# M0519SD3AE_breakout_v1.net
KiCad netlist of a schematic drawn in EAGLE
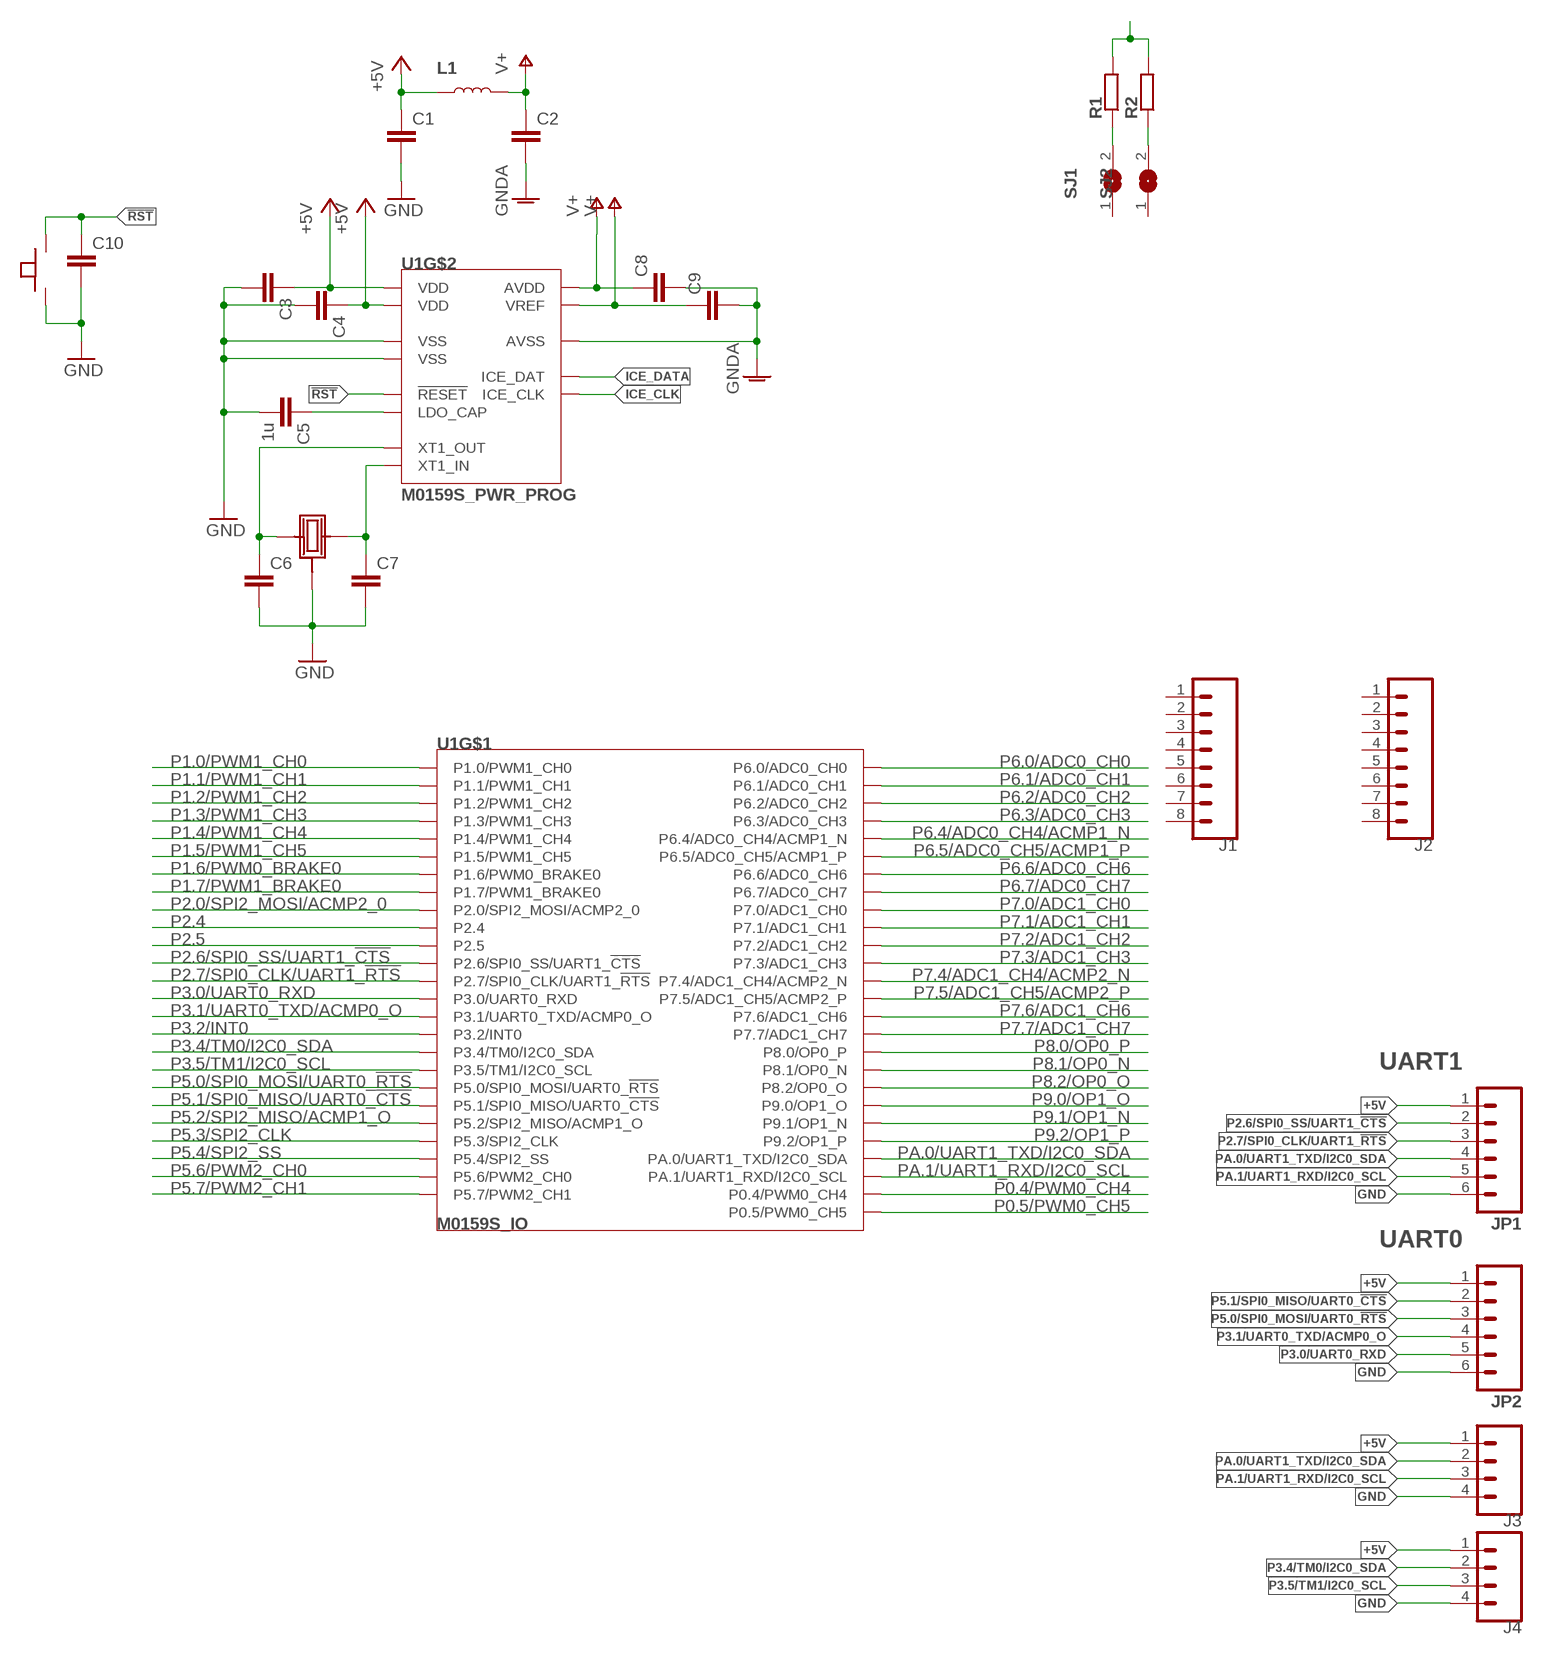
[diagram p0: schematic, sheet 1]

(export (version "E")
  (design (tool "Eeschema 10.0.6"))
  (components
    (comp (ref "C1")
      (value "CAP0603-CAP")
      (footprint "eagle-import:0603-CAP")
      (libsource (lib "eagle-import") (part "CAP0603-CAP"))
    )
    (comp (ref "C2")
      (value "CAP0603-CAP")
      (footprint "eagle-import:0603-CAP")
      (libsource (lib "eagle-import") (part "CAP0603-CAP"))
    )
    (comp (ref "C3")
      (value "CAP0603-CAP")
      (footprint "eagle-import:0603-CAP")
      (libsource (lib "eagle-import") (part "CAP0603-CAP"))
    )
    (comp (ref "C4")
      (value "CAP0603-CAP")
      (footprint "eagle-import:0603-CAP")
      (libsource (lib "eagle-import") (part "CAP0603-CAP"))
    )
    (comp (ref "C5")
      (value "1u")
      (footprint "eagle-import:0603-CAP")
      (libsource (lib "eagle-import") (part "CAP0603-CAP"))
    )
    (comp (ref "C6")
      (value "CAP0603-CAP")
      (footprint "eagle-import:0603-CAP")
      (libsource (lib "eagle-import") (part "CAP0603-CAP"))
    )
    (comp (ref "C7")
      (value "CAP0603-CAP")
      (footprint "eagle-import:0603-CAP")
      (libsource (lib "eagle-import") (part "CAP0603-CAP"))
    )
    (comp (ref "C8")
      (value "CAP0603-CAP")
      (footprint "eagle-import:0603-CAP")
      (libsource (lib "eagle-import") (part "CAP0603-CAP"))
    )
    (comp (ref "C9")
      (value "CAP0603-CAP")
      (footprint "eagle-import:0603-CAP")
      (libsource (lib "eagle-import") (part "CAP0603-CAP"))
    )
    (comp (ref "C10")
      (value "CAP0603-CAP")
      (footprint "eagle-import:0603-CAP")
      (libsource (lib "eagle-import") (part "CAP0603-CAP"))
    )
    (comp (ref "J1")
      (value "M08")
      (footprint "eagle-import:1X08")
      (libsource (lib "eagle-import") (part "M08"))
    )
    (comp (ref "J2")
      (value "M08")
      (footprint "eagle-import:1X08")
      (libsource (lib "eagle-import") (part "M08"))
    )
    (comp (ref "J3")
      (value "M04")
      (footprint "eagle-import:1X04")
      (libsource (lib "eagle-import") (part "M04"))
    )
    (comp (ref "J4")
      (value "M04")
      (footprint "eagle-import:1X04")
      (libsource (lib "eagle-import") (part "M04"))
    )
    (comp (ref "JP1")
      (value "M06LOCK")
      (footprint "eagle-import:1X06_LOCK")
      (libsource (lib "eagle-import") (part "M06LOCK"))
    )
    (comp (ref "JP2")
      (value "M06LOCK")
      (footprint "eagle-import:1X06_LOCK")
      (libsource (lib "eagle-import") (part "M06LOCK"))
    )
    (comp (ref "L1")
      (value "INDUCTOR_FB")
      (footprint "eagle-import:0603-FB")
      (libsource (lib "eagle-import") (part "INDUCTOR_FB"))
    )
    (comp (ref "R1")
      (value "RESISTOR0603-RES")
      (footprint "eagle-import:0603-RES")
      (libsource (lib "eagle-import") (part "RESISTOR0603-RES"))
    )
    (comp (ref "R2")
      (value "RESISTOR0603-RES")
      (footprint "eagle-import:0603-RES")
      (libsource (lib "eagle-import") (part "RESISTOR0603-RES"))
    )
    (comp (ref "SJ1") (value "SJ") (footprint "eagle-import:SJ") (libsource (lib "eagle-import") (part "SJ")))
    (comp (ref "SJ2") (value "SJ") (footprint "eagle-import:SJ") (libsource (lib "eagle-import") (part "SJ")))
    (comp (ref "U$1")
      (value "CRYSTAL_EPSON")
      (footprint "eagle-import:TSX3225")
      (libsource (lib "eagle-import") (part "CRYSTAL_EPSON"))
    )
    (comp (ref "U$2")
      (value "95C06B2GWRT")
      (footprint "eagle-import:PUSH-BUTTON-95C06B2GWRT")
      (libsource (lib "eagle-import") (part "95C06B2GWRT"))
    )
    (comp (ref "U1")
      (value "M0159S")
      (footprint "eagle-import:LQFP-64_7MMX7MMX1.6MM")
      (libsource (lib "eagle-import") (part "M0159S"))
    )
  )
  (nets
    (net (code "1") (name "+5V") (class "Default")
      (node (ref "C1") (pin "1") (pinfunction "1_1") (pintype "passive"))
      (node (ref "C3") (pin "1") (pinfunction "1_1") (pintype "passive"))
      (node (ref "C4") (pin "1") (pinfunction "1_1") (pintype "passive"))
      (node (ref "J3") (pin "1") (pinfunction "1_1") (pintype "passive"))
      (node (ref "J4") (pin "1") (pinfunction "1_1") (pintype "passive"))
      (node (ref "JP1") (pin "1") (pinfunction "1_1") (pintype "passive"))
      (node (ref "JP2") (pin "1") (pinfunction "1_1") (pintype "passive"))
      (node (ref "L1") (pin "1") (pinfunction "1_1") (pintype "passive"))
      (node (ref "U1") (pin "21") (pinfunction "VDD_21") (pintype "power_in"))
      (node (ref "U1") (pin "6") (pinfunction "VDD_6") (pintype "power_in"))
    )
    (net (code "2") (name "/P0.4{slash}PWM0_CH4") (class "Default")
      (node (ref "U1") (pin "30") (pinfunction "P0.4/PWM0_CH4_30") (pintype "bidirectional"))
    )
    (net (code "3") (name "/P0.5{slash}PWM0_CH5") (class "Default")
      (node (ref "U1") (pin "29") (pinfunction "P0.5/PWM0_CH5_29") (pintype "bidirectional"))
    )
    (net (code "4") (name "/P1.0{slash}PWM1_CH0") (class "Default")
      (node (ref "U1") (pin "18") (pinfunction "P1.0/PWM1_CH0_18") (pintype "bidirectional"))
    )
    (net (code "5") (name "/P1.1{slash}PWM1_CH1") (class "Default")
      (node (ref "U1") (pin "17") (pinfunction "P1.1/PWM1_CH1_17") (pintype "bidirectional"))
    )
    (net (code "6") (name "/P1.2{slash}PWM1_CH2") (class "Default")
      (node (ref "U1") (pin "16") (pinfunction "P1.2/PWM1_CH2_16") (pintype "bidirectional"))
    )
    (net (code "7") (name "/P1.3{slash}PWM1_CH3") (class "Default")
      (node (ref "U1") (pin "15") (pinfunction "P1.3/PWM1_CH3_15") (pintype "bidirectional"))
    )
    (net (code "8") (name "/P1.4{slash}PWM1_CH4") (class "Default")
      (node (ref "U1") (pin "14") (pinfunction "P1.4/PWM1_CH4_14") (pintype "bidirectional"))
    )
    (net (code "9") (name "/P1.5{slash}PWM1_CH5") (class "Default")
      (node (ref "U1") (pin "13") (pinfunction "P1.5/PWM1_CH5_13") (pintype "bidirectional"))
    )
    (net (code "10") (name "/P1.6{slash}PWM0_BRAKE0") (class "Default")
      (node (ref "U1") (pin "12") (pinfunction "P1.6/PWM0_BRAKE0_12") (pintype "bidirectional"))
    )
    (net (code "11") (name "/P1.7{slash}PWM1_BRAKE0") (class "Default")
      (node (ref "U1") (pin "4") (pinfunction "P1.7/PWM1_BRAKE0_4") (pintype "bidirectional"))
    )
    (net (code "12") (name "/P2.0{slash}SPI2_MOSI{slash}ACMP2_0") (class "Default")
      (node (ref "U1") (pin "31") (pinfunction "P2.0/SPI2_MOSI/ACMP2_0_31") (pintype "bidirectional"))
    )
    (net (code "13") (name "/P2.4") (class "Default")
      (node (ref "U1") (pin "28") (pinfunction "P2.4_28") (pintype "bidirectional"))
    )
    (net (code "14") (name "/P2.5") (class "Default")
      (node (ref "U1") (pin "27") (pinfunction "P2.5_27") (pintype "bidirectional"))
    )
    (net (code "15") (name "/P2.6{slash}SPI0_SS{slash}UART1_~{CTS}") (class "Default")
      (node (ref "JP1") (pin "2") (pinfunction "2_2") (pintype "passive"))
      (node (ref "U1") (pin "26") (pinfunction "P2.6/SPI0_SS/UART1_~{CTS}_26") (pintype "bidirectional"))
    )
    (net (code "16") (name "/P2.7{slash}SPI0_CLK{slash}UART1_~{RTS}") (class "Default")
      (node (ref "JP1") (pin "3") (pinfunction "3_3") (pintype "passive"))
      (node (ref "U1") (pin "25") (pinfunction "P2.7/SPI0_CLK/UART1_~{RTS}_25") (pintype "bidirectional"))
    )
    (net (code "17") (name "/P3.2{slash}INT0") (class "Default")
      (node (ref "U1") (pin "3") (pinfunction "P3.2/INT0_3") (pintype "bidirectional"))
    )
    (net (code "18") (name "/P5.0{slash}SPI0_MOSI{slash}UART0_~{RTS}") (class "Default")
      (node (ref "JP2") (pin "3") (pinfunction "3_3") (pintype "passive"))
      (node (ref "U1") (pin "23") (pinfunction "P5.0/SPI0_MOSI/UART0_~{RTS}_23") (pintype "bidirectional"))
    )
    (net (code "19") (name "/P5.1{slash}SPI0_MISO{slash}UART0_~{CTS}") (class "Default")
      (node (ref "JP2") (pin "2") (pinfunction "2_2") (pintype "passive"))
      (node (ref "U1") (pin "24") (pinfunction "P5.1/SPI0_MISO/UART0_~{CTS}_24") (pintype "bidirectional"))
    )
    (net (code "20") (name "/P5.2{slash}SPI2_MISO{slash}ACMP1_O") (class "Default")
      (node (ref "U1") (pin "32") (pinfunction "P5.2/SPI2_MISO/ACMP1_O_32") (pintype "bidirectional"))
    )
    (net (code "21") (name "/P5.3{slash}SPI2_CLK") (class "Default")
      (node (ref "U1") (pin "33") (pinfunction "P5.3/SPI2_CLK_33") (pintype "bidirectional"))
    )
    (net (code "22") (name "/P5.4{slash}SPI2_SS") (class "Default")
      (node (ref "U1") (pin "34") (pinfunction "P5.4/SPI2_SS_34") (pintype "bidirectional"))
    )
    (net (code "23") (name "/P5.6{slash}PWM2_CH0") (class "Default")
      (node (ref "U1") (pin "11") (pinfunction "P5.6/PWM2_CH0_11") (pintype "bidirectional"))
    )
    (net (code "24") (name "/P5.7{slash}PWM2_CH1") (class "Default")
      (node (ref "U1") (pin "10") (pinfunction "P5.7/PWM2_CH1_10") (pintype "bidirectional"))
    )
    (net (code "25") (name "/P6.0{slash}ADC0_CH0") (class "Default")
      (node (ref "U1") (pin "42") (pinfunction "P6.0/ADC0_CH0_42") (pintype "bidirectional"))
    )
    (net (code "26") (name "/P6.1{slash}ADC0_CH1") (class "Default")
      (node (ref "U1") (pin "41") (pinfunction "P6.1/ADC0_CH1_41") (pintype "bidirectional"))
    )
    (net (code "27") (name "/P6.2{slash}ADC0_CH2") (class "Default")
      (node (ref "U1") (pin "40") (pinfunction "P6.2/ADC0_CH2_40") (pintype "bidirectional"))
    )
    (net (code "28") (name "/P6.3{slash}ADC0_CH3") (class "Default")
      (node (ref "U1") (pin "39") (pinfunction "P6.3/ADC0_CH3_39") (pintype "bidirectional"))
    )
    (net (code "29") (name "/P6.4{slash}ADC0_CH4{slash}ACMP1_N") (class "Default")
      (node (ref "U1") (pin "38") (pinfunction "P6.4/ADC0_CH4/ACMP1_N_38") (pintype "bidirectional"))
    )
    (net (code "30") (name "/P6.5{slash}ADC0_CH5{slash}ACMP1_P") (class "Default")
      (node (ref "U1") (pin "37") (pinfunction "P6.5/ADC0_CH5/ACMP1_P_37") (pintype "bidirectional"))
    )
    (net (code "31") (name "/P6.6{slash}ADC0_CH6") (class "Default")
      (node (ref "U1") (pin "36") (pinfunction "P6.6/ADC0_CH6_36") (pintype "bidirectional"))
    )
    (net (code "32") (name "/P6.7{slash}ADC0_CH7") (class "Default")
      (node (ref "U1") (pin "35") (pinfunction "P6.7/ADC0_CH7_35") (pintype "bidirectional"))
    )
    (net (code "33") (name "/P7.0{slash}ADC1_CH0") (class "Default")
      (node (ref "U1") (pin "56") (pinfunction "P7.0/ADC1_CH0_56") (pintype "bidirectional"))
    )
    (net (code "34") (name "/P7.1{slash}ADC1_CH1") (class "Default")
      (node (ref "U1") (pin "55") (pinfunction "P7.1/ADC1_CH1_55") (pintype "bidirectional"))
    )
    (net (code "35") (name "/P7.2{slash}ADC1_CH2") (class "Default")
      (node (ref "U1") (pin "54") (pinfunction "P7.2/ADC1_CH2_54") (pintype "bidirectional"))
    )
    (net (code "36") (name "/P7.3{slash}ADC1_CH3") (class "Default")
      (node (ref "U1") (pin "53") (pinfunction "P7.3/ADC1_CH3_53") (pintype "bidirectional"))
    )
    (net (code "37") (name "/P7.4{slash}ADC1_CH4{slash}ACMP2_N") (class "Default")
      (node (ref "U1") (pin "52") (pinfunction "P7.4/ADC1_CH4/ACMP2_N_52") (pintype "bidirectional"))
    )
    (net (code "38") (name "/P7.5{slash}ADC1_CH5{slash}ACMP2_P") (class "Default")
      (node (ref "U1") (pin "51") (pinfunction "P7.5/ADC1_CH5/ACMP2_P_51") (pintype "bidirectional"))
    )
    (net (code "39") (name "/P7.6{slash}ADC1_CH6") (class "Default")
      (node (ref "U1") (pin "50") (pinfunction "P7.6/ADC1_CH6_50") (pintype "bidirectional"))
    )
    (net (code "40") (name "/P7.7{slash}ADC1_CH7") (class "Default")
      (node (ref "U1") (pin "49") (pinfunction "P7.7/ADC1_CH7_49") (pintype "bidirectional"))
    )
    (net (code "41") (name "/P8.0{slash}OP0_P") (class "Default")
      (node (ref "U1") (pin "45") (pinfunction "P8.0/OP0_P_45") (pintype "bidirectional"))
    )
    (net (code "42") (name "/P8.1{slash}OP0_N") (class "Default")
      (node (ref "U1") (pin "44") (pinfunction "P8.1/OP0_N_44") (pintype "bidirectional"))
    )
    (net (code "43") (name "/P8.2{slash}OP0_O") (class "Default")
      (node (ref "U1") (pin "43") (pinfunction "P8.2/OP0_O_43") (pintype "bidirectional"))
    )
    (net (code "44") (name "/P9.0{slash}OP1_O") (class "Default")
      (node (ref "U1") (pin "57") (pinfunction "P9.0/OP1_O_57") (pintype "bidirectional"))
    )
    (net (code "45") (name "/P9.1{slash}OP1_N") (class "Default")
      (node (ref "U1") (pin "58") (pinfunction "P9.1/OP1_N_58") (pintype "bidirectional"))
    )
    (net (code "46") (name "/P9.2{slash}OP1_P") (class "Default")
      (node (ref "U1") (pin "59") (pinfunction "P9.2/OP1_P_59") (pintype "bidirectional"))
    )
    (net (code "47") (name "/~{RST}") (class "Default")
      (node (ref "C10") (pin "1") (pinfunction "1_1") (pintype "passive"))
      (node (ref "U$2") (pin "P3") (pinfunction "B_P3") (pintype "passive"))
      (node (ref "U$2") (pin "P4") (pinfunction "B_P4") (pintype "passive"))
      (node (ref "U1") (pin "60") (pinfunction "~{RESET}_60") (pintype "bidirectional"))
    )
    (net (code "48") (name "GND") (class "Default")
      (node (ref "C1") (pin "2") (pinfunction "2_2") (pintype "passive"))
      (node (ref "C10") (pin "2") (pinfunction "2_2") (pintype "passive"))
      (node (ref "C3") (pin "2") (pinfunction "2_2") (pintype "passive"))
      (node (ref "C4") (pin "2") (pinfunction "2_2") (pintype "passive"))
      (node (ref "C5") (pin "2") (pinfunction "2_2") (pintype "passive"))
      (node (ref "C6") (pin "2") (pinfunction "2_2") (pintype "passive"))
      (node (ref "C7") (pin "2") (pinfunction "2_2") (pintype "passive"))
      (node (ref "J3") (pin "4") (pinfunction "4_4") (pintype "passive"))
      (node (ref "J4") (pin "4") (pinfunction "4_4") (pintype "passive"))
      (node (ref "JP1") (pin "6") (pinfunction "6_6") (pintype "passive"))
      (node (ref "JP2") (pin "6") (pinfunction "6_6") (pintype "passive"))
      (node (ref "U$1") (pin "2") (pinfunction "2_2") (pintype "power_in"))
      (node (ref "U$1") (pin "4") (pinfunction "2_4") (pintype "power_in"))
      (node (ref "U$2") (pin "P1") (pinfunction "A_P1") (pintype "passive"))
      (node (ref "U$2") (pin "P2") (pinfunction "A_P2") (pintype "passive"))
      (node (ref "U1") (pin "22") (pinfunction "VSS_22") (pintype "power_in"))
      (node (ref "U1") (pin "7") (pinfunction "VSS_7") (pintype "power_in"))
    )
    (net (code "49") (name "GNDA") (class "Default")
      (node (ref "C2") (pin "2") (pinfunction "2_2") (pintype "passive"))
      (node (ref "C8") (pin "2") (pinfunction "2_2") (pintype "passive"))
      (node (ref "C9") (pin "2") (pinfunction "2_2") (pintype "passive"))
      (node (ref "U1") (pin "46") (pinfunction "AVSS_46") (pintype "power_in"))
    )
    (net (code "50") (name "ICE_CLK") (class "Default")
      (node (ref "U1") (pin "64") (pinfunction "ICE_CLK_64") (pintype "bidirectional"))
    )
    (net (code "51") (name "ICE_DATA") (class "Default")
      (node (ref "U1") (pin "63") (pinfunction "ICE_DAT_63") (pintype "bidirectional"))
    )
    (net (code "52") (name "Net-(R1-Pad1)") (class "Default")
      (node (ref "R1") (pin "1") (pinfunction "1_1") (pintype "passive"))
      (node (ref "SJ1") (pin "2") (pinfunction "2_2") (pintype "passive"))
    )
    (net (code "53") (name "Net-(R1-Pad2)") (class "Default")
      (node (ref "R1") (pin "2") (pinfunction "2_2") (pintype "passive"))
      (node (ref "R2") (pin "2") (pinfunction "2_2") (pintype "passive"))
    )
    (net (code "54") (name "Net-(R2-Pad1)") (class "Default")
      (node (ref "R2") (pin "1") (pinfunction "1_1") (pintype "passive"))
      (node (ref "SJ2") (pin "2") (pinfunction "2_2") (pintype "passive"))
    )
    (net (code "55") (name "Net-(U1B-LDO_CAP)") (class "Default")
      (node (ref "C5") (pin "1") (pinfunction "1_1") (pintype "passive"))
      (node (ref "U1") (pin "5") (pinfunction "LDO_CAP_5") (pintype "power_in"))
    )
    (net (code "56") (name "Net-(U1B-XT1_IN)") (class "Default")
      (node (ref "C7") (pin "1") (pinfunction "1_1") (pintype "passive"))
      (node (ref "U$1") (pin "1") (pinfunction "1_1") (pintype "bidirectional"))
      (node (ref "U1") (pin "62") (pinfunction "XT1_IN_62") (pintype "bidirectional"))
    )
    (net (code "57") (name "Net-(U1B-XT1_OUT)") (class "Default")
      (node (ref "C6") (pin "1") (pinfunction "1_1") (pintype "passive"))
      (node (ref "U$1") (pin "3") (pinfunction "3_3") (pintype "bidirectional"))
      (node (ref "U1") (pin "61") (pinfunction "XT1_OUT_61") (pintype "bidirectional"))
    )
    (net (code "58") (name "P3.0{slash}UART0_RXD") (class "Default")
      (node (ref "JP2") (pin "5") (pinfunction "5_5") (pintype "passive"))
      (node (ref "U1") (pin "19") (pinfunction "P3.0/UART0_RXD_19") (pintype "bidirectional"))
    )
    (net (code "59") (name "P3.1{slash}UART0_TXD{slash}ACMP0_O") (class "Default")
      (node (ref "JP2") (pin "4") (pinfunction "4_4") (pintype "passive"))
      (node (ref "U1") (pin "20") (pinfunction "P3.1/UART0_TXD/ACMP0_O_20") (pintype "bidirectional"))
    )
    (net (code "60") (name "P3.4{slash}TM0{slash}I2C0_SDA") (class "Default")
      (node (ref "J4") (pin "2") (pinfunction "2_2") (pintype "passive"))
      (node (ref "U1") (pin "2") (pinfunction "P3.4/TM0/I2C0_SDA_2") (pintype "bidirectional"))
    )
    (net (code "61") (name "P3.5{slash}TM1{slash}I2C0_SCL") (class "Default")
      (node (ref "J4") (pin "3") (pinfunction "3_3") (pintype "passive"))
      (node (ref "U1") (pin "1") (pinfunction "P3.5/TM1/I2C0_SCL_1") (pintype "bidirectional"))
    )
    (net (code "62") (name "PA.0{slash}UART1_TXD{slash}I2C0_SDA") (class "Default")
      (node (ref "J3") (pin "2") (pinfunction "2_2") (pintype "passive"))
      (node (ref "JP1") (pin "4") (pinfunction "4_4") (pintype "passive"))
      (node (ref "U1") (pin "9") (pinfunction "PA.0/UART1_TXD/I2C0_SDA_9") (pintype "bidirectional"))
    )
    (net (code "63") (name "PA.1{slash}UART1_RXD{slash}I2C0_SCL") (class "Default")
      (node (ref "J3") (pin "3") (pinfunction "3_3") (pintype "passive"))
      (node (ref "JP1") (pin "5") (pinfunction "5_5") (pintype "passive"))
      (node (ref "U1") (pin "8") (pinfunction "PA.1/UART1_RXD/I2C0_SCL_8") (pintype "bidirectional"))
    )
    (net (code "64") (name "V+") (class "Default")
      (node (ref "C2") (pin "1") (pinfunction "1_1") (pintype "passive"))
      (node (ref "C8") (pin "1") (pinfunction "1_1") (pintype "passive"))
      (node (ref "C9") (pin "1") (pinfunction "1_1") (pintype "passive"))
      (node (ref "L1") (pin "2") (pinfunction "2_2") (pintype "passive"))
      (node (ref "U1") (pin "47") (pinfunction "AVDD_47") (pintype "power_in"))
      (node (ref "U1") (pin "48") (pinfunction "VREF_48") (pintype "power_in"))
    )
    (net (code "65") (name "unconnected-(J1-Pad1)") (class "Default")
      (node (ref "J1") (pin "1") (pinfunction "1_1") (pintype "passive"))
    )
    (net (code "66") (name "unconnected-(J1-Pad2)") (class "Default")
      (node (ref "J1") (pin "2") (pinfunction "2_2") (pintype "passive"))
    )
    (net (code "67") (name "unconnected-(J1-Pad3)") (class "Default")
      (node (ref "J1") (pin "3") (pinfunction "3_3") (pintype "passive"))
    )
    (net (code "68") (name "unconnected-(J1-Pad4)") (class "Default")
      (node (ref "J1") (pin "4") (pinfunction "4_4") (pintype "passive"))
    )
    (net (code "69") (name "unconnected-(J1-Pad5)") (class "Default")
      (node (ref "J1") (pin "5") (pinfunction "5_5") (pintype "passive"))
    )
    (net (code "70") (name "unconnected-(J1-Pad6)") (class "Default")
      (node (ref "J1") (pin "6") (pinfunction "6_6") (pintype "passive"))
    )
    (net (code "71") (name "unconnected-(J1-Pad7)") (class "Default")
      (node (ref "J1") (pin "7") (pinfunction "7_7") (pintype "passive"))
    )
    (net (code "72") (name "unconnected-(J1-Pad8)") (class "Default")
      (node (ref "J1") (pin "8") (pinfunction "8_8") (pintype "passive"))
    )
    (net (code "73") (name "unconnected-(J2-Pad1)") (class "Default")
      (node (ref "J2") (pin "1") (pinfunction "1_1") (pintype "passive"))
    )
    (net (code "74") (name "unconnected-(J2-Pad2)") (class "Default")
      (node (ref "J2") (pin "2") (pinfunction "2_2") (pintype "passive"))
    )
    (net (code "75") (name "unconnected-(J2-Pad3)") (class "Default")
      (node (ref "J2") (pin "3") (pinfunction "3_3") (pintype "passive"))
    )
    (net (code "76") (name "unconnected-(J2-Pad4)") (class "Default")
      (node (ref "J2") (pin "4") (pinfunction "4_4") (pintype "passive"))
    )
    (net (code "77") (name "unconnected-(J2-Pad5)") (class "Default")
      (node (ref "J2") (pin "5") (pinfunction "5_5") (pintype "passive"))
    )
    (net (code "78") (name "unconnected-(J2-Pad6)") (class "Default")
      (node (ref "J2") (pin "6") (pinfunction "6_6") (pintype "passive"))
    )
    (net (code "79") (name "unconnected-(J2-Pad7)") (class "Default")
      (node (ref "J2") (pin "7") (pinfunction "7_7") (pintype "passive"))
    )
    (net (code "80") (name "unconnected-(J2-Pad8)") (class "Default")
      (node (ref "J2") (pin "8") (pinfunction "8_8") (pintype "passive"))
    )
    (net (code "81") (name "unconnected-(SJ1-Pad1)") (class "Default")
      (node (ref "SJ1") (pin "1") (pinfunction "1_1") (pintype "passive"))
    )
    (net (code "82") (name "unconnected-(SJ2-Pad1)") (class "Default")
      (node (ref "SJ2") (pin "1") (pinfunction "1_1") (pintype "passive"))
    )
  )
)
